# TOP.net
KiCad netlist of a schematic drawn in Altium Designer
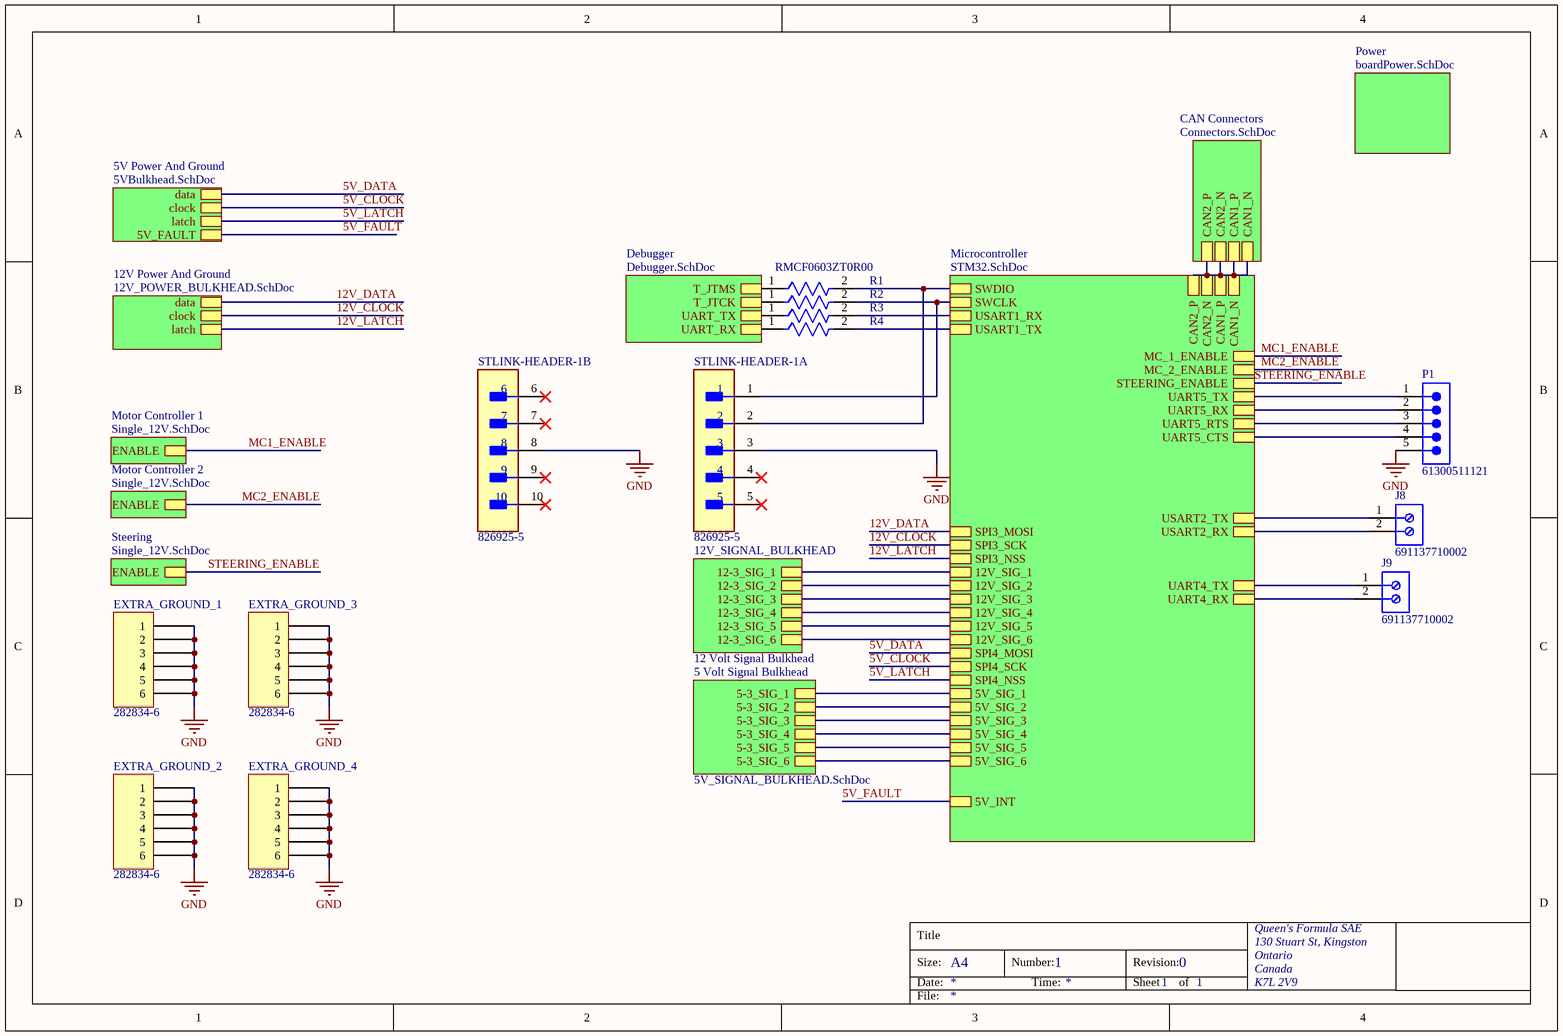
[diagram p0: TOP.SchDoc]

(export (version "E")
  (design (tool "Eeschema 10.0.6"))
  (components
    (comp (ref "EXTRA_GROUND_1")
      (value "282834-6")
      (footprint "TE 282834-6")
      (description "TERM BLK 6P SIDE ENT 2.54MM PCB")
      (fields (field (name "MANUFACTURER") "TE Connectivity AMP Connectors") (field (name "VOLTAGE") "150V"))
      (libsource (lib "Celestial Altium Library - altium_library") (part "6 Pin"))
    )
    (comp (ref "EXTRA_GROUND_2")
      (value "282834-6")
      (footprint "TE 282834-6")
      (description "TERM BLK 6P SIDE ENT 2.54MM PCB")
      (fields (field (name "MANUFACTURER") "TE Connectivity AMP Connectors") (field (name "VOLTAGE") "150V"))
      (libsource (lib "Celestial Altium Library - altium_library") (part "6 Pin"))
    )
    (comp (ref "EXTRA_GROUND_3")
      (value "282834-6")
      (footprint "TE 282834-6")
      (description "TERM BLK 6P SIDE ENT 2.54MM PCB")
      (fields (field (name "MANUFACTURER") "TE Connectivity AMP Connectors") (field (name "VOLTAGE") "150V"))
      (libsource (lib "Celestial Altium Library - altium_library") (part "6 Pin"))
    )
    (comp (ref "EXTRA_GROUND_4")
      (value "282834-6")
      (footprint "TE 282834-6")
      (description "TERM BLK 6P SIDE ENT 2.54MM PCB")
      (fields (field (name "MANUFACTURER") "TE Connectivity AMP Connectors") (field (name "VOLTAGE") "150V"))
      (libsource (lib "Celestial Altium Library - altium_library") (part "6 Pin"))
    )
    (comp (ref "J8")
      (value "691137710002")
      (footprint "691137710002")
      (libsource (lib "Altium Content Vault") (part "TBL - 1R - 02P - Screw"))
    )
    (comp (ref "J9")
      (value "691137710002")
      (footprint "691137710002")
      (libsource (lib "Altium Content Vault") (part "TBL - 1R - 02P - Screw"))
    )
    (comp (ref "P1")
      (value "61300511121")
      (footprint "61300511121")
      (libsource (lib "Altium Content Vault") (part "Header_Male_1R_05P"))
    )
    (comp (ref "R1")
      (value "RMCF0603ZT0R00")
      (footprint "FP-RMCF0603-MFG")
      (description "RES 0 OHM JUMPER 1/10W 0603")
      (fields
        (field (name "OCTOPART") "https://octopart.com/rmcf0603zt0r00-stackpole+electronics-19213618")
        (field (name "MANUFACTURER") "Stackpole")
      )
      (libsource (lib "Altium Content Vault") (part "1029c3af85768c4190bb7ad29bc67b5"))
    )
    (comp (ref "R2")
      (value "RMCF0603ZT0R00")
      (footprint "FP-RMCF0603-MFG")
      (description "RES 0 OHM JUMPER 1/10W 0603")
      (fields
        (field (name "OCTOPART") "https://octopart.com/rmcf0603zt0r00-stackpole+electronics-19213618")
        (field (name "MANUFACTURER") "Stackpole")
      )
      (libsource (lib "Altium Content Vault") (part "1029c3af85768c4190bb7ad29bc67b5"))
    )
    (comp (ref "R3")
      (value "RMCF0603ZT0R00")
      (footprint "FP-RMCF0603-MFG")
      (description "RES 0 OHM JUMPER 1/10W 0603")
      (fields
        (field (name "OCTOPART") "https://octopart.com/rmcf0603zt0r00-stackpole+electronics-19213618")
        (field (name "MANUFACTURER") "Stackpole")
      )
      (libsource (lib "Altium Content Vault") (part "1029c3af85768c4190bb7ad29bc67b5"))
    )
    (comp (ref "R4")
      (value "RMCF0603ZT0R00")
      (footprint "FP-RMCF0603-MFG")
      (description "RES 0 OHM JUMPER 1/10W 0603")
      (fields
        (field (name "OCTOPART") "https://octopart.com/rmcf0603zt0r00-stackpole+electronics-19213618")
        (field (name "MANUFACTURER") "Stackpole")
      )
      (libsource (lib "Altium Content Vault") (part "1029c3af85768c4190bb7ad29bc67b5"))
    )
    (comp (ref "STLINK-HEADER-1")
      (value "826925-5")
      (footprint "FP-826925-5-MFG")
      (description "CONN HEADER VERT 10POS 2.54MM")
      (fields
        (field (name "OCTOPART") "https://octopart.com/826925-5-te+connectivity-41836231")
        (field (name "MANUFACTURER") "TE Connectivity")
      )
      (libsource (lib "Altium Content Vault") (part "de255ff815dec4fe6d5caee7def00c9"))
    )
  )
  (nets
    (net (code "24") (name "/SWCLK") (class "Default")
      (node (ref "R2") (pin "2") (pinfunction "2_2") (pintype "passive"))
      (node (ref "STLINK-HEADER-1") (pin "1") (pinfunction "1_1") (pintype "passive"))
    )
    (net (code "25") (name "/SWDIO") (class "Default")
      (node (ref "R1") (pin "2") (pinfunction "2_2") (pintype "passive"))
      (node (ref "STLINK-HEADER-1") (pin "2") (pinfunction "2_2") (pintype "passive"))
    )
    (net (code "26") (name "/T_JTCK") (class "Default")
      (node (ref "R2") (pin "1") (pinfunction "1_1") (pintype "passive"))
    )
    (net (code "27") (name "/T_JTMS") (class "Default")
      (node (ref "R1") (pin "1") (pinfunction "1_1") (pintype "passive"))
    )
    (net (code "28") (name "/UART4_RX") (class "Default")
      (node (ref "J9") (pin "2") (pinfunction "2_2") (pintype "passive"))
    )
    (net (code "29") (name "/UART4_TX") (class "Default")
      (node (ref "J9") (pin "1") (pinfunction "1_1") (pintype "passive"))
    )
    (net (code "30") (name "/UART5_CTS") (class "Default")
      (node (ref "P1") (pin "4") (pinfunction "4_4") (pintype "passive"))
    )
    (net (code "31") (name "/UART5_RTS") (class "Default")
      (node (ref "P1") (pin "3") (pinfunction "3_3") (pintype "passive"))
    )
    (net (code "32") (name "/UART5_RX") (class "Default")
      (node (ref "P1") (pin "2") (pinfunction "2_2") (pintype "passive"))
    )
    (net (code "33") (name "/UART5_TX") (class "Default")
      (node (ref "P1") (pin "1") (pinfunction "1_1") (pintype "passive"))
    )
    (net (code "34") (name "/UART_RX") (class "Default")
      (node (ref "R4") (pin "1") (pinfunction "1_1") (pintype "passive"))
    )
    (net (code "35") (name "/UART_TX") (class "Default")
      (node (ref "R3") (pin "1") (pinfunction "1_1") (pintype "passive"))
    )
    (net (code "36") (name "/USART1_RX") (class "Default")
      (node (ref "R3") (pin "2") (pinfunction "2_2") (pintype "passive"))
    )
    (net (code "37") (name "/USART1_TX") (class "Default")
      (node (ref "R4") (pin "2") (pinfunction "2_2") (pintype "passive"))
    )
    (net (code "38") (name "/USART2_RX") (class "Default")
      (node (ref "J8") (pin "2") (pinfunction "2_2") (pintype "passive"))
    )
    (net (code "39") (name "/USART2_TX") (class "Default")
      (node (ref "J8") (pin "1") (pinfunction "1_1") (pintype "passive"))
    )
    (net (code "40") (name "GND") (class "Default")
      (node (ref "EXTRA_GROUND_1") (pin "1") (pinfunction "1_1") (pintype "passive"))
      (node (ref "EXTRA_GROUND_1") (pin "2") (pinfunction "2_2") (pintype "passive"))
      (node (ref "EXTRA_GROUND_1") (pin "3") (pinfunction "3_3") (pintype "passive"))
      (node (ref "EXTRA_GROUND_1") (pin "4") (pinfunction "4_4") (pintype "passive"))
      (node (ref "EXTRA_GROUND_1") (pin "5") (pinfunction "5_5") (pintype "passive"))
      (node (ref "EXTRA_GROUND_1") (pin "6") (pinfunction "6_6") (pintype "passive"))
      (node (ref "EXTRA_GROUND_2") (pin "1") (pinfunction "1_1") (pintype "passive"))
      (node (ref "EXTRA_GROUND_2") (pin "2") (pinfunction "2_2") (pintype "passive"))
      (node (ref "EXTRA_GROUND_2") (pin "3") (pinfunction "3_3") (pintype "passive"))
      (node (ref "EXTRA_GROUND_2") (pin "4") (pinfunction "4_4") (pintype "passive"))
      (node (ref "EXTRA_GROUND_2") (pin "5") (pinfunction "5_5") (pintype "passive"))
      (node (ref "EXTRA_GROUND_2") (pin "6") (pinfunction "6_6") (pintype "passive"))
      (node (ref "EXTRA_GROUND_3") (pin "1") (pinfunction "1_1") (pintype "passive"))
      (node (ref "EXTRA_GROUND_3") (pin "2") (pinfunction "2_2") (pintype "passive"))
      (node (ref "EXTRA_GROUND_3") (pin "3") (pinfunction "3_3") (pintype "passive"))
      (node (ref "EXTRA_GROUND_3") (pin "4") (pinfunction "4_4") (pintype "passive"))
      (node (ref "EXTRA_GROUND_3") (pin "5") (pinfunction "5_5") (pintype "passive"))
      (node (ref "EXTRA_GROUND_3") (pin "6") (pinfunction "6_6") (pintype "passive"))
      (node (ref "EXTRA_GROUND_4") (pin "1") (pinfunction "1_1") (pintype "passive"))
      (node (ref "EXTRA_GROUND_4") (pin "2") (pinfunction "2_2") (pintype "passive"))
      (node (ref "EXTRA_GROUND_4") (pin "3") (pinfunction "3_3") (pintype "passive"))
      (node (ref "EXTRA_GROUND_4") (pin "4") (pinfunction "4_4") (pintype "passive"))
      (node (ref "EXTRA_GROUND_4") (pin "5") (pinfunction "5_5") (pintype "passive"))
      (node (ref "EXTRA_GROUND_4") (pin "6") (pinfunction "6_6") (pintype "passive"))
      (node (ref "P1") (pin "5") (pinfunction "5_5") (pintype "passive"))
      (node (ref "STLINK-HEADER-1") (pin "3") (pinfunction "3_3") (pintype "passive"))
      (node (ref "STLINK-HEADER-1") (pin "8") (pinfunction "8_8") (pintype "passive"))
    )
    (net (code "41") (name "unconnected-(STLINK-HEADER-1-Pad4)") (class "Default")
      (node (ref "STLINK-HEADER-1") (pin "4") (pinfunction "4_4") (pintype "passive+no_connect"))
    )
    (net (code "42") (name "unconnected-(STLINK-HEADER-1-Pad5)") (class "Default")
      (node (ref "STLINK-HEADER-1") (pin "5") (pinfunction "5_5") (pintype "passive+no_connect"))
    )
    (net (code "43") (name "unconnected-(STLINK-HEADER-1-Pad6)") (class "Default")
      (node (ref "STLINK-HEADER-1") (pin "6") (pinfunction "6_6") (pintype "passive+no_connect"))
    )
    (net (code "44") (name "unconnected-(STLINK-HEADER-1-Pad7)") (class "Default")
      (node (ref "STLINK-HEADER-1") (pin "7") (pinfunction "7_7") (pintype "passive+no_connect"))
    )
    (net (code "45") (name "unconnected-(STLINK-HEADER-1-Pad9)") (class "Default")
      (node (ref "STLINK-HEADER-1") (pin "9") (pinfunction "9_9") (pintype "passive+no_connect"))
    )
    (net (code "46") (name "unconnected-(STLINK-HEADER-1-Pad10)") (class "Default")
      (node (ref "STLINK-HEADER-1") (pin "10") (pinfunction "10_10") (pintype "passive+no_connect"))
    )
  )
)
